# GSM_Modem_Core.net
KiCad netlist of a schematic drawn in Altium Designer
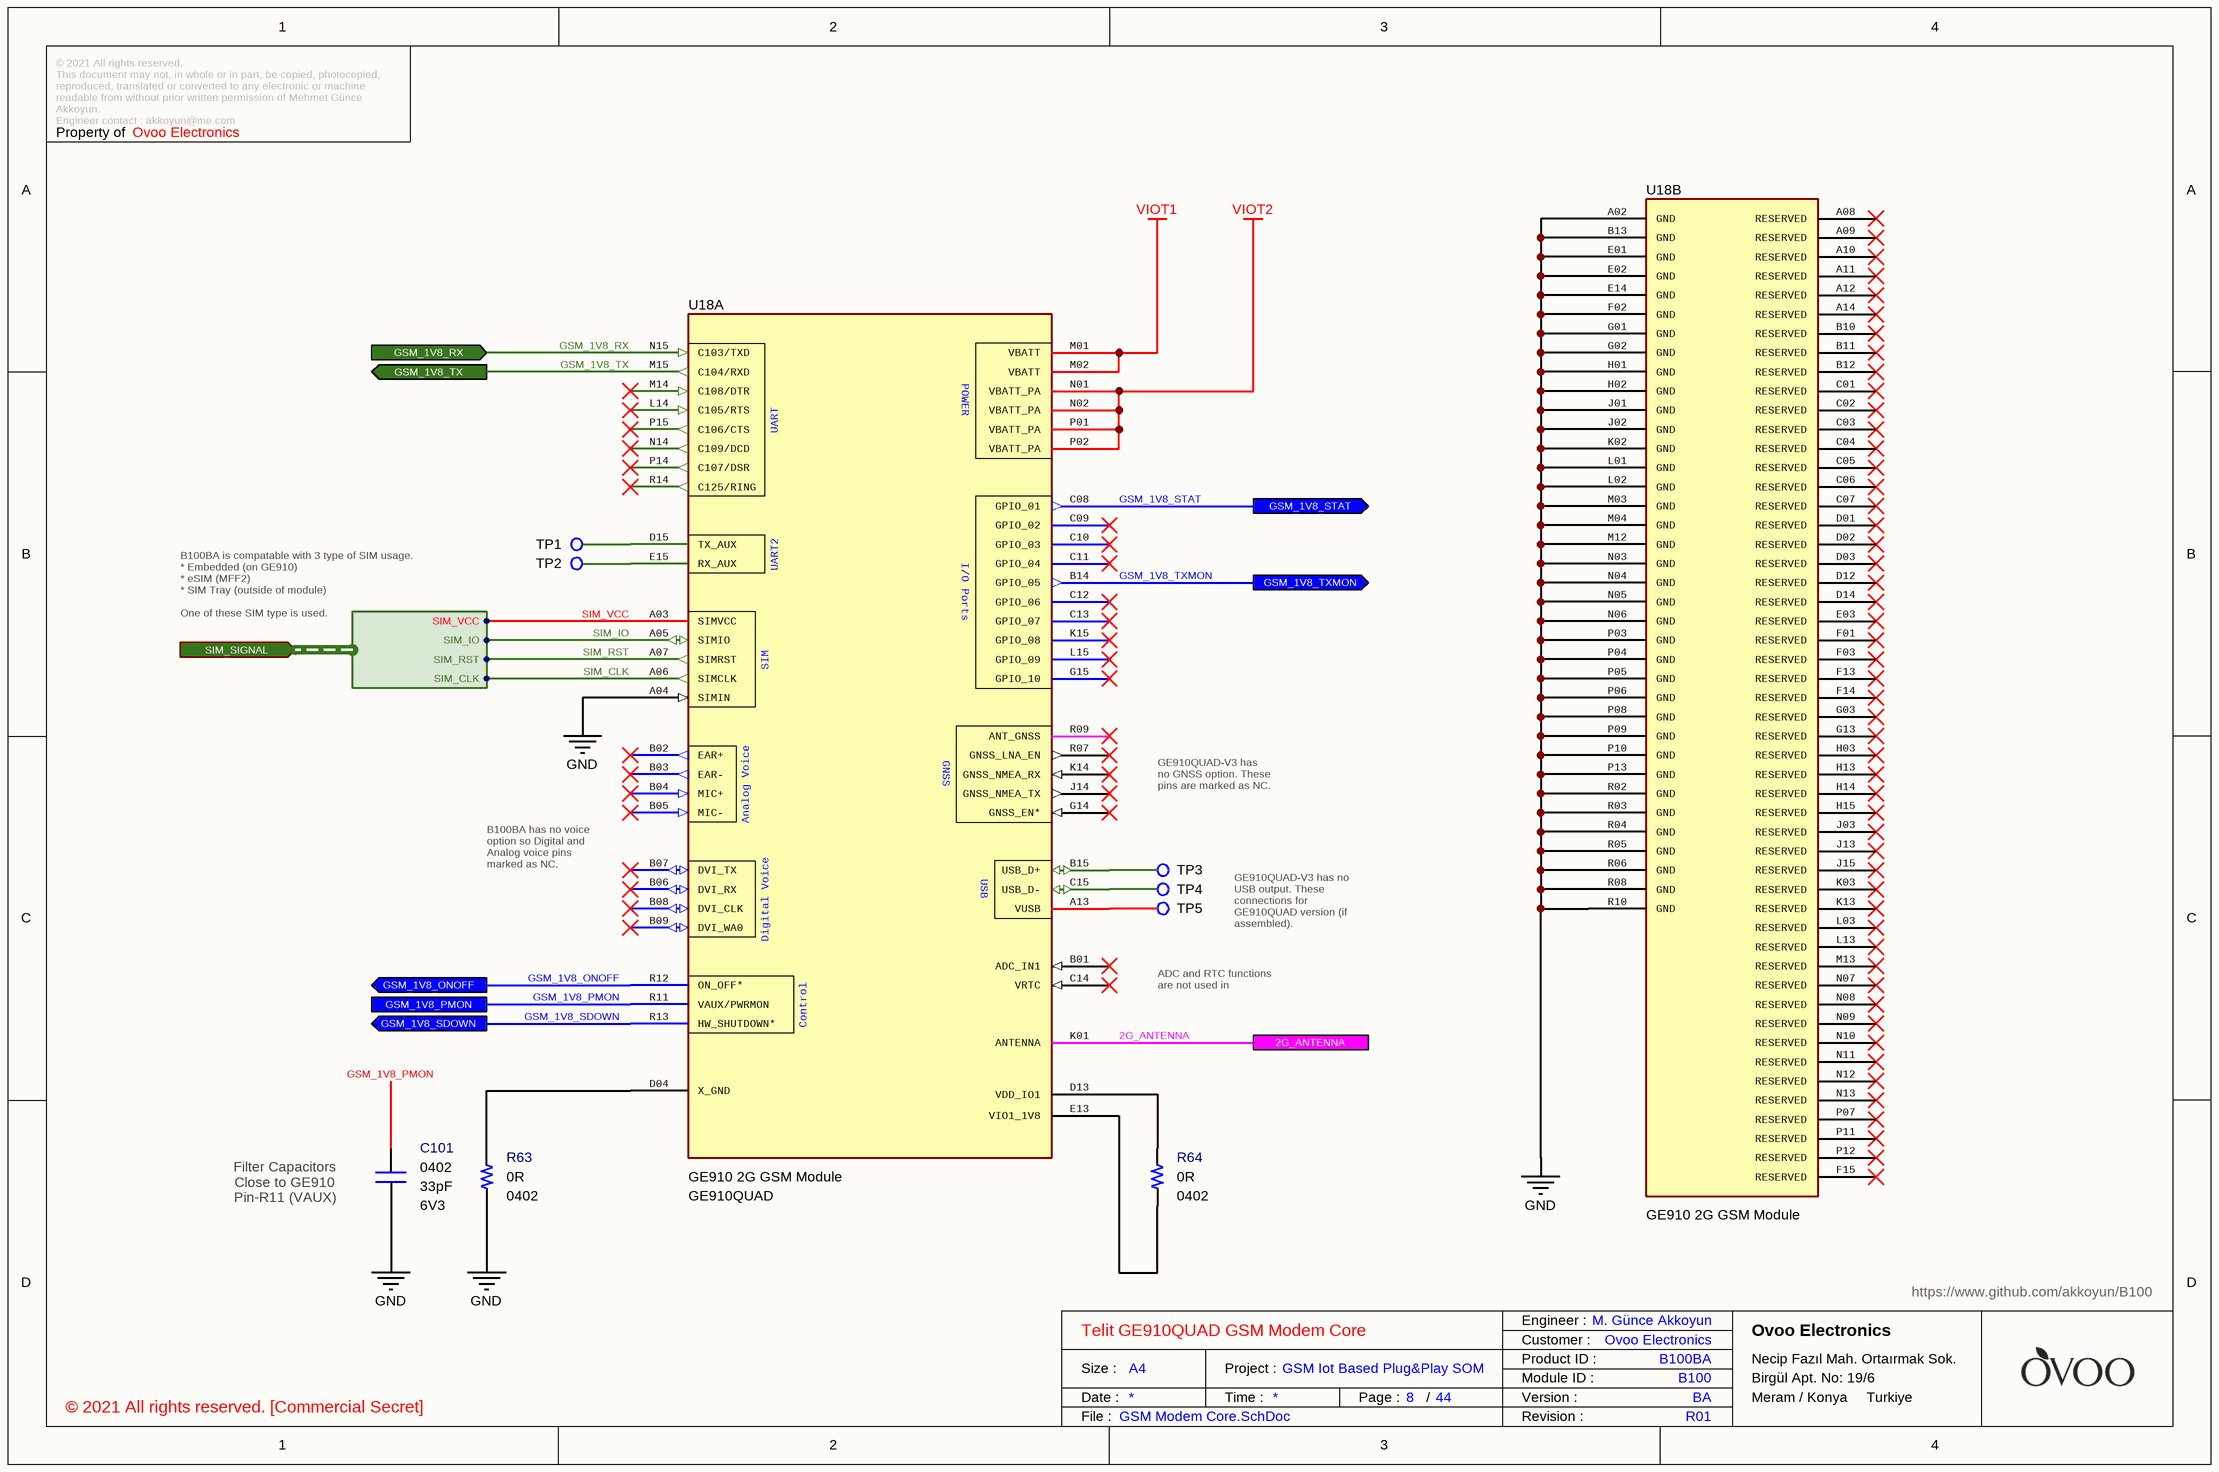
[diagram p0: GSM Modem Core.SchDoc]

(export (version "E")
  (design (tool "Eeschema 10.0.6"))
  (components
    (comp (ref "C101")
      (value "33pF")
      (footprint "CAPACITOR_0402")
      (description "Capacitor - 33pF [0402] (Ceramic)")
      (fields
        (field (name "TOLERANCE") "10%")
        (field (name "CASE") "0402")
        (field (name "VOLTAGE") "6V3")
        (field (name "MANUFACTURER PART NUMBER") "C0402C330J9RACAUTO")
      )
      (libsource (lib "Ovoo_Library") (part "Capacitor - 33pF [0402-6V3]"))
    )
    (comp (ref "R63")
      (value "0R")
      (footprint "RESISTOR_0402")
      (description "Thick Film Resistors - SMD 1/16 W 0 Ohms")
      (fields
        (field (name "CASE") "0402")
        (field (name "MANUFACTURER PART NUMBER") "CRCW04020000Z0ED")
        (field (name "MOUSER PART NUMBER") "71-CRCW0402-0-E3")
      )
      (libsource (lib "Ovoo_Library") (part "Resistor - 0R"))
    )
    (comp (ref "R64")
      (value "0R")
      (footprint "RESISTOR_0402")
      (description "Thick Film Resistors - SMD 1/16 W 0 Ohms")
      (fields
        (field (name "CASE") "0402")
        (field (name "MANUFACTURER PART NUMBER") "CRCW04020000Z0ED")
        (field (name "MOUSER PART NUMBER") "71-CRCW0402-0-E3")
      )
      (libsource (lib "Ovoo_Library") (part "Resistor - 0R"))
    )
    (comp (ref "TP1")
      (value "PCB - Test Point")
      (footprint "Test_Point")
      (description "Test Point")
      (libsource (lib "Ovoo_Library") (part "PCB - Test Point"))
    )
    (comp (ref "TP2")
      (value "PCB - Test Point")
      (footprint "Test_Point")
      (description "Test Point")
      (libsource (lib "Ovoo_Library") (part "PCB - Test Point"))
    )
    (comp (ref "TP3")
      (value "PCB - Test Point")
      (footprint "Test_Point")
      (description "Test Point")
      (libsource (lib "Ovoo_Library") (part "PCB - Test Point"))
    )
    (comp (ref "TP4")
      (value "PCB - Test Point")
      (footprint "Test_Point")
      (description "Test Point")
      (libsource (lib "Ovoo_Library") (part "PCB - Test Point"))
    )
    (comp (ref "TP5")
      (value "PCB - Test Point")
      (footprint "Test_Point")
      (description "Test Point")
      (libsource (lib "Ovoo_Library") (part "PCB - Test Point"))
    )
    (comp (ref "U18")
      (value "GE910 2G GSM Module")
      (footprint "GE910 2G GSM Modem")
      (description "Telit GE910 GPRS/UMTS Module")
      (fields (field (name "MANUFACTURER PART NUMBER") "GE910QUAD"))
      (libsource (lib "Ovoo_Library") (part "IC - Telit GE910QUAD"))
    )
  )
  (nets
    (net (code "2") (name "/2G_ANTENNA") (class "Default")
      (node (ref "U18") (pin "K01") (pinfunction "ANTENNA_K01") (pintype "passive"))
    )
    (net (code "3") (name "/GSM_1V8_ONOFF") (class "Default")
      (node (ref "U18") (pin "R12") (pinfunction "ON_OFF*_R12") (pintype "open_collector"))
    )
    (net (code "4") (name "/GSM_1V8_PMON") (class "Default")
      (node (ref "C101") (pin "2") (pinfunction "2_2") (pintype "passive"))
      (node (ref "U18") (pin "R11") (pinfunction "VAUX/PWRMON_R11") (pintype "passive"))
    )
    (net (code "5") (name "/GSM_1V8_RX") (class "Default")
      (node (ref "U18") (pin "N15") (pinfunction "C103/TXD_N15") (pintype "input"))
    )
    (net (code "6") (name "/GSM_1V8_SDOWN") (class "Default")
      (node (ref "U18") (pin "R13") (pinfunction "HW_SHUTDOWN*_R13") (pintype "open_collector"))
    )
    (net (code "7") (name "/GSM_1V8_STAT") (class "Default")
      (node (ref "U18") (pin "C08") (pinfunction "GPIO_01_C08") (pintype "output"))
    )
    (net (code "8") (name "/GSM_1V8_TX") (class "Default")
      (node (ref "U18") (pin "M15") (pinfunction "C104/RXD_M15") (pintype "output"))
    )
    (net (code "9") (name "/GSM_1V8_TXMON") (class "Default")
      (node (ref "U18") (pin "B14") (pinfunction "GPIO_05_B14") (pintype "output"))
    )
    (net (code "10") (name "/SIM_CLK") (class "Default")
      (node (ref "U18") (pin "A06") (pinfunction "SIMCLK_A06") (pintype "output"))
    )
    (net (code "11") (name "/SIM_IO") (class "Default")
      (node (ref "U18") (pin "A05") (pinfunction "SIMIO_A05") (pintype "bidirectional"))
    )
    (net (code "12") (name "/SIM_RST") (class "Default")
      (node (ref "U18") (pin "A07") (pinfunction "SIMRST_A07") (pintype "output"))
    )
    (net (code "13") (name "/SIM_VCC") (class "Default")
      (node (ref "U18") (pin "A03") (pinfunction "SIMVCC_A03") (pintype "power_in"))
    )
    (net (code "15") (name "GND") (class "Default")
      (node (ref "C101") (pin "1") (pinfunction "1_1") (pintype "passive"))
      (node (ref "R63") (pin "1") (pinfunction "1_1") (pintype "passive"))
      (node (ref "U18") (pin "A02") (pinfunction "GND_A02") (pintype "power_in"))
      (node (ref "U18") (pin "A04") (pinfunction "SIMIN_A04") (pintype "input"))
      (node (ref "U18") (pin "B13") (pinfunction "GND_B13") (pintype "power_in"))
      (node (ref "U18") (pin "E01") (pinfunction "GND_E01") (pintype "power_in"))
      (node (ref "U18") (pin "E02") (pinfunction "GND_E02") (pintype "power_in"))
      (node (ref "U18") (pin "E14") (pinfunction "GND_E14") (pintype "power_in"))
      (node (ref "U18") (pin "F02") (pinfunction "GND_F02") (pintype "power_in"))
      (node (ref "U18") (pin "G01") (pinfunction "GND_G01") (pintype "power_in"))
      (node (ref "U18") (pin "G02") (pinfunction "GND_G02") (pintype "power_in"))
      (node (ref "U18") (pin "H01") (pinfunction "GND_H01") (pintype "power_in"))
      (node (ref "U18") (pin "H02") (pinfunction "GND_H02") (pintype "power_in"))
      (node (ref "U18") (pin "J01") (pinfunction "GND_J01") (pintype "power_in"))
      (node (ref "U18") (pin "J02") (pinfunction "GND_J02") (pintype "power_in"))
      (node (ref "U18") (pin "K02") (pinfunction "GND_K02") (pintype "power_in"))
      (node (ref "U18") (pin "L01") (pinfunction "GND_L01") (pintype "power_in"))
      (node (ref "U18") (pin "L02") (pinfunction "GND_L02") (pintype "power_in"))
      (node (ref "U18") (pin "M03") (pinfunction "GND_M03") (pintype "power_in"))
      (node (ref "U18") (pin "M04") (pinfunction "GND_M04") (pintype "power_in"))
      (node (ref "U18") (pin "M12") (pinfunction "GND_M12") (pintype "power_in"))
      (node (ref "U18") (pin "N03") (pinfunction "GND_N03") (pintype "power_in"))
      (node (ref "U18") (pin "N04") (pinfunction "GND_N04") (pintype "power_in"))
      (node (ref "U18") (pin "N05") (pinfunction "GND_N05") (pintype "power_in"))
      (node (ref "U18") (pin "N06") (pinfunction "GND_N06") (pintype "power_in"))
      (node (ref "U18") (pin "P03") (pinfunction "GND_P03") (pintype "power_in"))
      (node (ref "U18") (pin "P04") (pinfunction "GND_P04") (pintype "power_in"))
      (node (ref "U18") (pin "P05") (pinfunction "GND_P05") (pintype "power_in"))
      (node (ref "U18") (pin "P06") (pinfunction "GND_P06") (pintype "power_in"))
      (node (ref "U18") (pin "P08") (pinfunction "GND_P08") (pintype "power_in"))
      (node (ref "U18") (pin "P09") (pinfunction "GND_P09") (pintype "power_in"))
      (node (ref "U18") (pin "P10") (pinfunction "GND_P10") (pintype "power_in"))
      (node (ref "U18") (pin "P13") (pinfunction "GND_P13") (pintype "power_in"))
      (node (ref "U18") (pin "R02") (pinfunction "GND_R02") (pintype "power_in"))
      (node (ref "U18") (pin "R03") (pinfunction "GND_R03") (pintype "power_in"))
      (node (ref "U18") (pin "R04") (pinfunction "GND_R04") (pintype "power_in"))
      (node (ref "U18") (pin "R05") (pinfunction "GND_R05") (pintype "power_in"))
      (node (ref "U18") (pin "R06") (pinfunction "GND_R06") (pintype "power_in"))
      (node (ref "U18") (pin "R08") (pinfunction "GND_R08") (pintype "power_in"))
      (node (ref "U18") (pin "R10") (pinfunction "GND_R10") (pintype "power_in"))
    )
    (net (code "16") (name "Net-(U18A-RX_AUX)") (class "Default")
      (node (ref "TP2") (pin "1") (pinfunction "1_1") (pintype "passive"))
      (node (ref "U18") (pin "E15") (pinfunction "RX_AUX_E15") (pintype "passive"))
    )
    (net (code "17") (name "Net-(U18A-TX_AUX)") (class "Default")
      (node (ref "TP1") (pin "1") (pinfunction "1_1") (pintype "passive"))
      (node (ref "U18") (pin "D15") (pinfunction "TX_AUX_D15") (pintype "passive"))
    )
    (net (code "18") (name "Net-(U18A-USB_D+)") (class "Default")
      (node (ref "TP3") (pin "1") (pinfunction "1_1") (pintype "passive"))
      (node (ref "U18") (pin "B15") (pinfunction "USB_D+_B15") (pintype "bidirectional"))
    )
    (net (code "19") (name "Net-(U18A-USB_D-)") (class "Default")
      (node (ref "TP4") (pin "1") (pinfunction "1_1") (pintype "passive"))
      (node (ref "U18") (pin "C15") (pinfunction "USB_D-_C15") (pintype "bidirectional"))
    )
    (net (code "20") (name "Net-(U18A-VDD_IO1)") (class "Default")
      (node (ref "R64") (pin "2") (pinfunction "2_2") (pintype "passive"))
      (node (ref "U18") (pin "D13") (pinfunction "VDD_IO1_D13") (pintype "passive"))
    )
    (net (code "21") (name "Net-(U18A-VIO1_1V8)") (class "Default")
      (node (ref "R64") (pin "1") (pinfunction "1_1") (pintype "passive"))
      (node (ref "U18") (pin "E13") (pinfunction "VIO1_1V8_E13") (pintype "passive"))
    )
    (net (code "22") (name "Net-(U18A-VUSB)") (class "Default")
      (node (ref "TP5") (pin "1") (pinfunction "1_1") (pintype "passive"))
      (node (ref "U18") (pin "A13") (pinfunction "VUSB_A13") (pintype "passive"))
    )
    (net (code "23") (name "Net-(U18A-X_GND)") (class "Default")
      (node (ref "R63") (pin "2") (pinfunction "2_2") (pintype "passive"))
      (node (ref "U18") (pin "D04") (pinfunction "X_GND_D04") (pintype "power_in"))
    )
    (net (code "24") (name "VIOT1") (class "Default")
      (node (ref "U18") (pin "M01") (pinfunction "VBATT_M01") (pintype "power_in"))
      (node (ref "U18") (pin "M02") (pinfunction "VBATT_M02") (pintype "power_in"))
    )
    (net (code "25") (name "VIOT2") (class "Default")
      (node (ref "U18") (pin "N01") (pinfunction "VBATT_PA_N01") (pintype "power_in"))
      (node (ref "U18") (pin "N02") (pinfunction "VBATT_PA_N02") (pintype "power_in"))
      (node (ref "U18") (pin "P01") (pinfunction "VBATT_PA_P01") (pintype "power_in"))
      (node (ref "U18") (pin "P02") (pinfunction "VBATT_PA_P02") (pintype "power_in"))
    )
    (net (code "26") (name "unconnected-(U18A-ADC_IN1-PadB01)") (class "Default")
      (node (ref "U18") (pin "B01") (pinfunction "ADC_IN1_B01") (pintype "input+no_connect"))
    )
    (net (code "27") (name "unconnected-(U18A-ANT_GNSS-PadR09)") (class "Default")
      (node (ref "U18") (pin "R09") (pinfunction "ANT_GNSS_R09") (pintype "passive+no_connect"))
    )
    (net (code "28") (name "unconnected-(U18A-C105{slash}RTS-PadL14)") (class "Default")
      (node (ref "U18") (pin "L14") (pinfunction "C105/RTS_L14") (pintype "input+no_connect"))
    )
    (net (code "29") (name "unconnected-(U18A-C106{slash}CTS-PadP15)") (class "Default")
      (node (ref "U18") (pin "P15") (pinfunction "C106/CTS_P15") (pintype "output+no_connect"))
    )
    (net (code "30") (name "unconnected-(U18A-C107{slash}DSR-PadP14)") (class "Default")
      (node (ref "U18") (pin "P14") (pinfunction "C107/DSR_P14") (pintype "output+no_connect"))
    )
    (net (code "31") (name "unconnected-(U18A-C108{slash}DTR-PadM14)") (class "Default")
      (node (ref "U18") (pin "M14") (pinfunction "C108/DTR_M14") (pintype "input+no_connect"))
    )
    (net (code "32") (name "unconnected-(U18A-C109{slash}DCD-PadN14)") (class "Default")
      (node (ref "U18") (pin "N14") (pinfunction "C109/DCD_N14") (pintype "output+no_connect"))
    )
    (net (code "33") (name "unconnected-(U18A-C125{slash}RING-PadR14)") (class "Default")
      (node (ref "U18") (pin "R14") (pinfunction "C125/RING_R14") (pintype "output+no_connect"))
    )
    (net (code "34") (name "unconnected-(U18A-DVI_CLK-PadB08)") (class "Default")
      (node (ref "U18") (pin "B08") (pinfunction "DVI_CLK_B08") (pintype "bidirectional+no_connect"))
    )
    (net (code "35") (name "unconnected-(U18A-DVI_RX-PadB06)") (class "Default")
      (node (ref "U18") (pin "B06") (pinfunction "DVI_RX_B06") (pintype "bidirectional+no_connect"))
    )
    (net (code "36") (name "unconnected-(U18A-DVI_TX-PadB07)") (class "Default")
      (node (ref "U18") (pin "B07") (pinfunction "DVI_TX_B07") (pintype "bidirectional+no_connect"))
    )
    (net (code "37") (name "unconnected-(U18A-DVI_WA0-PadB09)") (class "Default")
      (node (ref "U18") (pin "B09") (pinfunction "DVI_WA0_B09") (pintype "bidirectional+no_connect"))
    )
    (net (code "38") (name "unconnected-(U18A-EAR+-PadB02)") (class "Default")
      (node (ref "U18") (pin "B02") (pinfunction "EAR+_B02") (pintype "output+no_connect"))
    )
    (net (code "39") (name "unconnected-(U18A-EAR--PadB03)") (class "Default")
      (node (ref "U18") (pin "B03") (pinfunction "EAR-_B03") (pintype "output+no_connect"))
    )
    (net (code "40") (name "unconnected-(U18A-GNSS_EN*-PadG14)") (class "Default")
      (node (ref "U18") (pin "G14") (pinfunction "GNSS_EN*_G14") (pintype "input+no_connect"))
    )
    (net (code "41") (name "unconnected-(U18A-GNSS_LNA_EN-PadR07)") (class "Default")
      (node (ref "U18") (pin "R07") (pinfunction "GNSS_LNA_EN_R07") (pintype "output+no_connect"))
    )
    (net (code "42") (name "unconnected-(U18A-GNSS_NMEA_RX-PadK14)") (class "Default")
      (node (ref "U18") (pin "K14") (pinfunction "GNSS_NMEA_RX_K14") (pintype "input+no_connect"))
    )
    (net (code "43") (name "unconnected-(U18A-GNSS_NMEA_TX-PadJ14)") (class "Default")
      (node (ref "U18") (pin "J14") (pinfunction "GNSS_NMEA_TX_J14") (pintype "output+no_connect"))
    )
    (net (code "44") (name "unconnected-(U18A-GPIO_02-PadC09)") (class "Default")
      (node (ref "U18") (pin "C09") (pinfunction "GPIO_02_C09") (pintype "passive+no_connect"))
    )
    (net (code "45") (name "unconnected-(U18A-GPIO_03-PadC10)") (class "Default")
      (node (ref "U18") (pin "C10") (pinfunction "GPIO_03_C10") (pintype "passive+no_connect"))
    )
    (net (code "46") (name "unconnected-(U18A-GPIO_04-PadC11)") (class "Default")
      (node (ref "U18") (pin "C11") (pinfunction "GPIO_04_C11") (pintype "passive+no_connect"))
    )
    (net (code "47") (name "unconnected-(U18A-GPIO_06-PadC12)") (class "Default")
      (node (ref "U18") (pin "C12") (pinfunction "GPIO_06_C12") (pintype "passive+no_connect"))
    )
    (net (code "48") (name "unconnected-(U18A-GPIO_07-PadC13)") (class "Default")
      (node (ref "U18") (pin "C13") (pinfunction "GPIO_07_C13") (pintype "passive+no_connect"))
    )
    (net (code "49") (name "unconnected-(U18A-GPIO_08-PadK15)") (class "Default")
      (node (ref "U18") (pin "K15") (pinfunction "GPIO_08_K15") (pintype "passive+no_connect"))
    )
    (net (code "50") (name "unconnected-(U18A-GPIO_09-PadL15)") (class "Default")
      (node (ref "U18") (pin "L15") (pinfunction "GPIO_09_L15") (pintype "passive+no_connect"))
    )
    (net (code "51") (name "unconnected-(U18A-GPIO_10-PadG15)") (class "Default")
      (node (ref "U18") (pin "G15") (pinfunction "GPIO_10_G15") (pintype "passive+no_connect"))
    )
    (net (code "52") (name "unconnected-(U18A-MIC+-PadB04)") (class "Default")
      (node (ref "U18") (pin "B04") (pinfunction "MIC+_B04") (pintype "input+no_connect"))
    )
    (net (code "53") (name "unconnected-(U18A-MIC--PadB05)") (class "Default")
      (node (ref "U18") (pin "B05") (pinfunction "MIC-_B05") (pintype "input+no_connect"))
    )
    (net (code "54") (name "unconnected-(U18A-VRTC-PadC14)") (class "Default")
      (node (ref "U18") (pin "C14") (pinfunction "VRTC_C14") (pintype "input+no_connect"))
    )
    (net (code "55") (name "unconnected-(U18B-RESERVED-PadA08)") (class "Default")
      (node (ref "U18") (pin "A08") (pinfunction "RESERVED_A08") (pintype "passive+no_connect"))
    )
    (net (code "56") (name "unconnected-(U18B-RESERVED-PadA09)") (class "Default")
      (node (ref "U18") (pin "A09") (pinfunction "RESERVED_A09") (pintype "passive+no_connect"))
    )
    (net (code "57") (name "unconnected-(U18B-RESERVED-PadA10)") (class "Default")
      (node (ref "U18") (pin "A10") (pinfunction "RESERVED_A10") (pintype "passive+no_connect"))
    )
    (net (code "58") (name "unconnected-(U18B-RESERVED-PadA11)") (class "Default")
      (node (ref "U18") (pin "A11") (pinfunction "RESERVED_A11") (pintype "passive+no_connect"))
    )
    (net (code "59") (name "unconnected-(U18B-RESERVED-PadA12)") (class "Default")
      (node (ref "U18") (pin "A12") (pinfunction "RESERVED_A12") (pintype "passive+no_connect"))
    )
    (net (code "60") (name "unconnected-(U18B-RESERVED-PadA14)") (class "Default")
      (node (ref "U18") (pin "A14") (pinfunction "RESERVED_A14") (pintype "passive+no_connect"))
    )
    (net (code "61") (name "unconnected-(U18B-RESERVED-PadB10)") (class "Default")
      (node (ref "U18") (pin "B10") (pinfunction "RESERVED_B10") (pintype "passive+no_connect"))
    )
    (net (code "62") (name "unconnected-(U18B-RESERVED-PadB11)") (class "Default")
      (node (ref "U18") (pin "B11") (pinfunction "RESERVED_B11") (pintype "passive+no_connect"))
    )
    (net (code "63") (name "unconnected-(U18B-RESERVED-PadB12)") (class "Default")
      (node (ref "U18") (pin "B12") (pinfunction "RESERVED_B12") (pintype "passive+no_connect"))
    )
    (net (code "64") (name "unconnected-(U18B-RESERVED-PadC01)") (class "Default")
      (node (ref "U18") (pin "C01") (pinfunction "RESERVED_C01") (pintype "passive+no_connect"))
    )
    (net (code "65") (name "unconnected-(U18B-RESERVED-PadC02)") (class "Default")
      (node (ref "U18") (pin "C02") (pinfunction "RESERVED_C02") (pintype "passive+no_connect"))
    )
    (net (code "66") (name "unconnected-(U18B-RESERVED-PadC03)") (class "Default")
      (node (ref "U18") (pin "C03") (pinfunction "RESERVED_C03") (pintype "passive+no_connect"))
    )
    (net (code "67") (name "unconnected-(U18B-RESERVED-PadC04)") (class "Default")
      (node (ref "U18") (pin "C04") (pinfunction "RESERVED_C04") (pintype "passive+no_connect"))
    )
    (net (code "68") (name "unconnected-(U18B-RESERVED-PadC05)") (class "Default")
      (node (ref "U18") (pin "C05") (pinfunction "RESERVED_C05") (pintype "passive+no_connect"))
    )
    (net (code "69") (name "unconnected-(U18B-RESERVED-PadC06)") (class "Default")
      (node (ref "U18") (pin "C06") (pinfunction "RESERVED_C06") (pintype "passive+no_connect"))
    )
    (net (code "70") (name "unconnected-(U18B-RESERVED-PadC07)") (class "Default")
      (node (ref "U18") (pin "C07") (pinfunction "RESERVED_C07") (pintype "passive+no_connect"))
    )
    (net (code "71") (name "unconnected-(U18B-RESERVED-PadD01)") (class "Default")
      (node (ref "U18") (pin "D01") (pinfunction "RESERVED_D01") (pintype "passive+no_connect"))
    )
    (net (code "72") (name "unconnected-(U18B-RESERVED-PadD02)") (class "Default")
      (node (ref "U18") (pin "D02") (pinfunction "RESERVED_D02") (pintype "passive+no_connect"))
    )
    (net (code "73") (name "unconnected-(U18B-RESERVED-PadD03)") (class "Default")
      (node (ref "U18") (pin "D03") (pinfunction "RESERVED_D03") (pintype "passive+no_connect"))
    )
    (net (code "74") (name "unconnected-(U18B-RESERVED-PadD12)") (class "Default")
      (node (ref "U18") (pin "D12") (pinfunction "RESERVED_D12") (pintype "passive+no_connect"))
    )
    (net (code "75") (name "unconnected-(U18B-RESERVED-PadD14)") (class "Default")
      (node (ref "U18") (pin "D14") (pinfunction "RESERVED_D14") (pintype "passive+no_connect"))
    )
    (net (code "76") (name "unconnected-(U18B-RESERVED-PadE03)") (class "Default")
      (node (ref "U18") (pin "E03") (pinfunction "RESERVED_E03") (pintype "passive+no_connect"))
    )
    (net (code "77") (name "unconnected-(U18B-RESERVED-PadF01)") (class "Default")
      (node (ref "U18") (pin "F01") (pinfunction "RESERVED_F01") (pintype "passive+no_connect"))
    )
    (net (code "78") (name "unconnected-(U18B-RESERVED-PadF03)") (class "Default")
      (node (ref "U18") (pin "F03") (pinfunction "RESERVED_F03") (pintype "passive+no_connect"))
    )
    (net (code "79") (name "unconnected-(U18B-RESERVED-PadF13)") (class "Default")
      (node (ref "U18") (pin "F13") (pinfunction "RESERVED_F13") (pintype "passive+no_connect"))
    )
    (net (code "80") (name "unconnected-(U18B-RESERVED-PadF14)") (class "Default")
      (node (ref "U18") (pin "F14") (pinfunction "RESERVED_F14") (pintype "passive+no_connect"))
    )
    (net (code "81") (name "unconnected-(U18B-RESERVED-PadF15)") (class "Default")
      (node (ref "U18") (pin "F15") (pinfunction "RESERVED_F15") (pintype "passive+no_connect"))
    )
    (net (code "82") (name "unconnected-(U18B-RESERVED-PadG03)") (class "Default")
      (node (ref "U18") (pin "G03") (pinfunction "RESERVED_G03") (pintype "passive+no_connect"))
    )
    (net (code "83") (name "unconnected-(U18B-RESERVED-PadG13)") (class "Default")
      (node (ref "U18") (pin "G13") (pinfunction "RESERVED_G13") (pintype "passive+no_connect"))
    )
    (net (code "84") (name "unconnected-(U18B-RESERVED-PadH03)") (class "Default")
      (node (ref "U18") (pin "H03") (pinfunction "RESERVED_H03") (pintype "passive+no_connect"))
    )
    (net (code "85") (name "unconnected-(U18B-RESERVED-PadH13)") (class "Default")
      (node (ref "U18") (pin "H13") (pinfunction "RESERVED_H13") (pintype "passive+no_connect"))
    )
    (net (code "86") (name "unconnected-(U18B-RESERVED-PadH14)") (class "Default")
      (node (ref "U18") (pin "H14") (pinfunction "RESERVED_H14") (pintype "passive+no_connect"))
    )
    (net (code "87") (name "unconnected-(U18B-RESERVED-PadH15)") (class "Default")
      (node (ref "U18") (pin "H15") (pinfunction "RESERVED_H15") (pintype "passive+no_connect"))
    )
    (net (code "88") (name "unconnected-(U18B-RESERVED-PadJ03)") (class "Default")
      (node (ref "U18") (pin "J03") (pinfunction "RESERVED_J03") (pintype "passive+no_connect"))
    )
    (net (code "89") (name "unconnected-(U18B-RESERVED-PadJ13)") (class "Default")
      (node (ref "U18") (pin "J13") (pinfunction "RESERVED_J13") (pintype "passive+no_connect"))
    )
    (net (code "90") (name "unconnected-(U18B-RESERVED-PadJ15)") (class "Default")
      (node (ref "U18") (pin "J15") (pinfunction "RESERVED_J15") (pintype "passive+no_connect"))
    )
    (net (code "91") (name "unconnected-(U18B-RESERVED-PadK03)") (class "Default")
      (node (ref "U18") (pin "K03") (pinfunction "RESERVED_K03") (pintype "passive+no_connect"))
    )
    (net (code "92") (name "unconnected-(U18B-RESERVED-PadK13)") (class "Default")
      (node (ref "U18") (pin "K13") (pinfunction "RESERVED_K13") (pintype "passive+no_connect"))
    )
    (net (code "93") (name "unconnected-(U18B-RESERVED-PadL03)") (class "Default")
      (node (ref "U18") (pin "L03") (pinfunction "RESERVED_L03") (pintype "passive+no_connect"))
    )
    (net (code "94") (name "unconnected-(U18B-RESERVED-PadL13)") (class "Default")
      (node (ref "U18") (pin "L13") (pinfunction "RESERVED_L13") (pintype "passive+no_connect"))
    )
    (net (code "95") (name "unconnected-(U18B-RESERVED-PadM13)") (class "Default")
      (node (ref "U18") (pin "M13") (pinfunction "RESERVED_M13") (pintype "passive+no_connect"))
    )
    (net (code "96") (name "unconnected-(U18B-RESERVED-PadN07)") (class "Default")
      (node (ref "U18") (pin "N07") (pinfunction "RESERVED_N07") (pintype "passive+no_connect"))
    )
    (net (code "97") (name "unconnected-(U18B-RESERVED-PadN08)") (class "Default")
      (node (ref "U18") (pin "N08") (pinfunction "RESERVED_N08") (pintype "passive+no_connect"))
    )
    (net (code "98") (name "unconnected-(U18B-RESERVED-PadN09)") (class "Default")
      (node (ref "U18") (pin "N09") (pinfunction "RESERVED_N09") (pintype "passive+no_connect"))
    )
    (net (code "99") (name "unconnected-(U18B-RESERVED-PadN10)") (class "Default")
      (node (ref "U18") (pin "N10") (pinfunction "RESERVED_N10") (pintype "passive+no_connect"))
    )
    (net (code "100") (name "unconnected-(U18B-RESERVED-PadN11)") (class "Default")
      (node (ref "U18") (pin "N11") (pinfunction "RESERVED_N11") (pintype "passive+no_connect"))
    )
    (net (code "101") (name "unconnected-(U18B-RESERVED-PadN12)") (class "Default")
      (node (ref "U18") (pin "N12") (pinfunction "RESERVED_N12") (pintype "passive+no_connect"))
    )
    (net (code "102") (name "unconnected-(U18B-RESERVED-PadN13)") (class "Default")
      (node (ref "U18") (pin "N13") (pinfunction "RESERVED_N13") (pintype "passive+no_connect"))
    )
    (net (code "103") (name "unconnected-(U18B-RESERVED-PadP07)") (class "Default")
      (node (ref "U18") (pin "P07") (pinfunction "RESERVED_P07") (pintype "passive+no_connect"))
    )
    (net (code "104") (name "unconnected-(U18B-RESERVED-PadP11)") (class "Default")
      (node (ref "U18") (pin "P11") (pinfunction "RESERVED_P11") (pintype "passive+no_connect"))
    )
    (net (code "105") (name "unconnected-(U18B-RESERVED-PadP12)") (class "Default")
      (node (ref "U18") (pin "P12") (pinfunction "RESERVED_P12") (pintype "passive+no_connect"))
    )
  )
)
